# Sheet1.net
KiCad netlist of a schematic drawn in Altium Designer
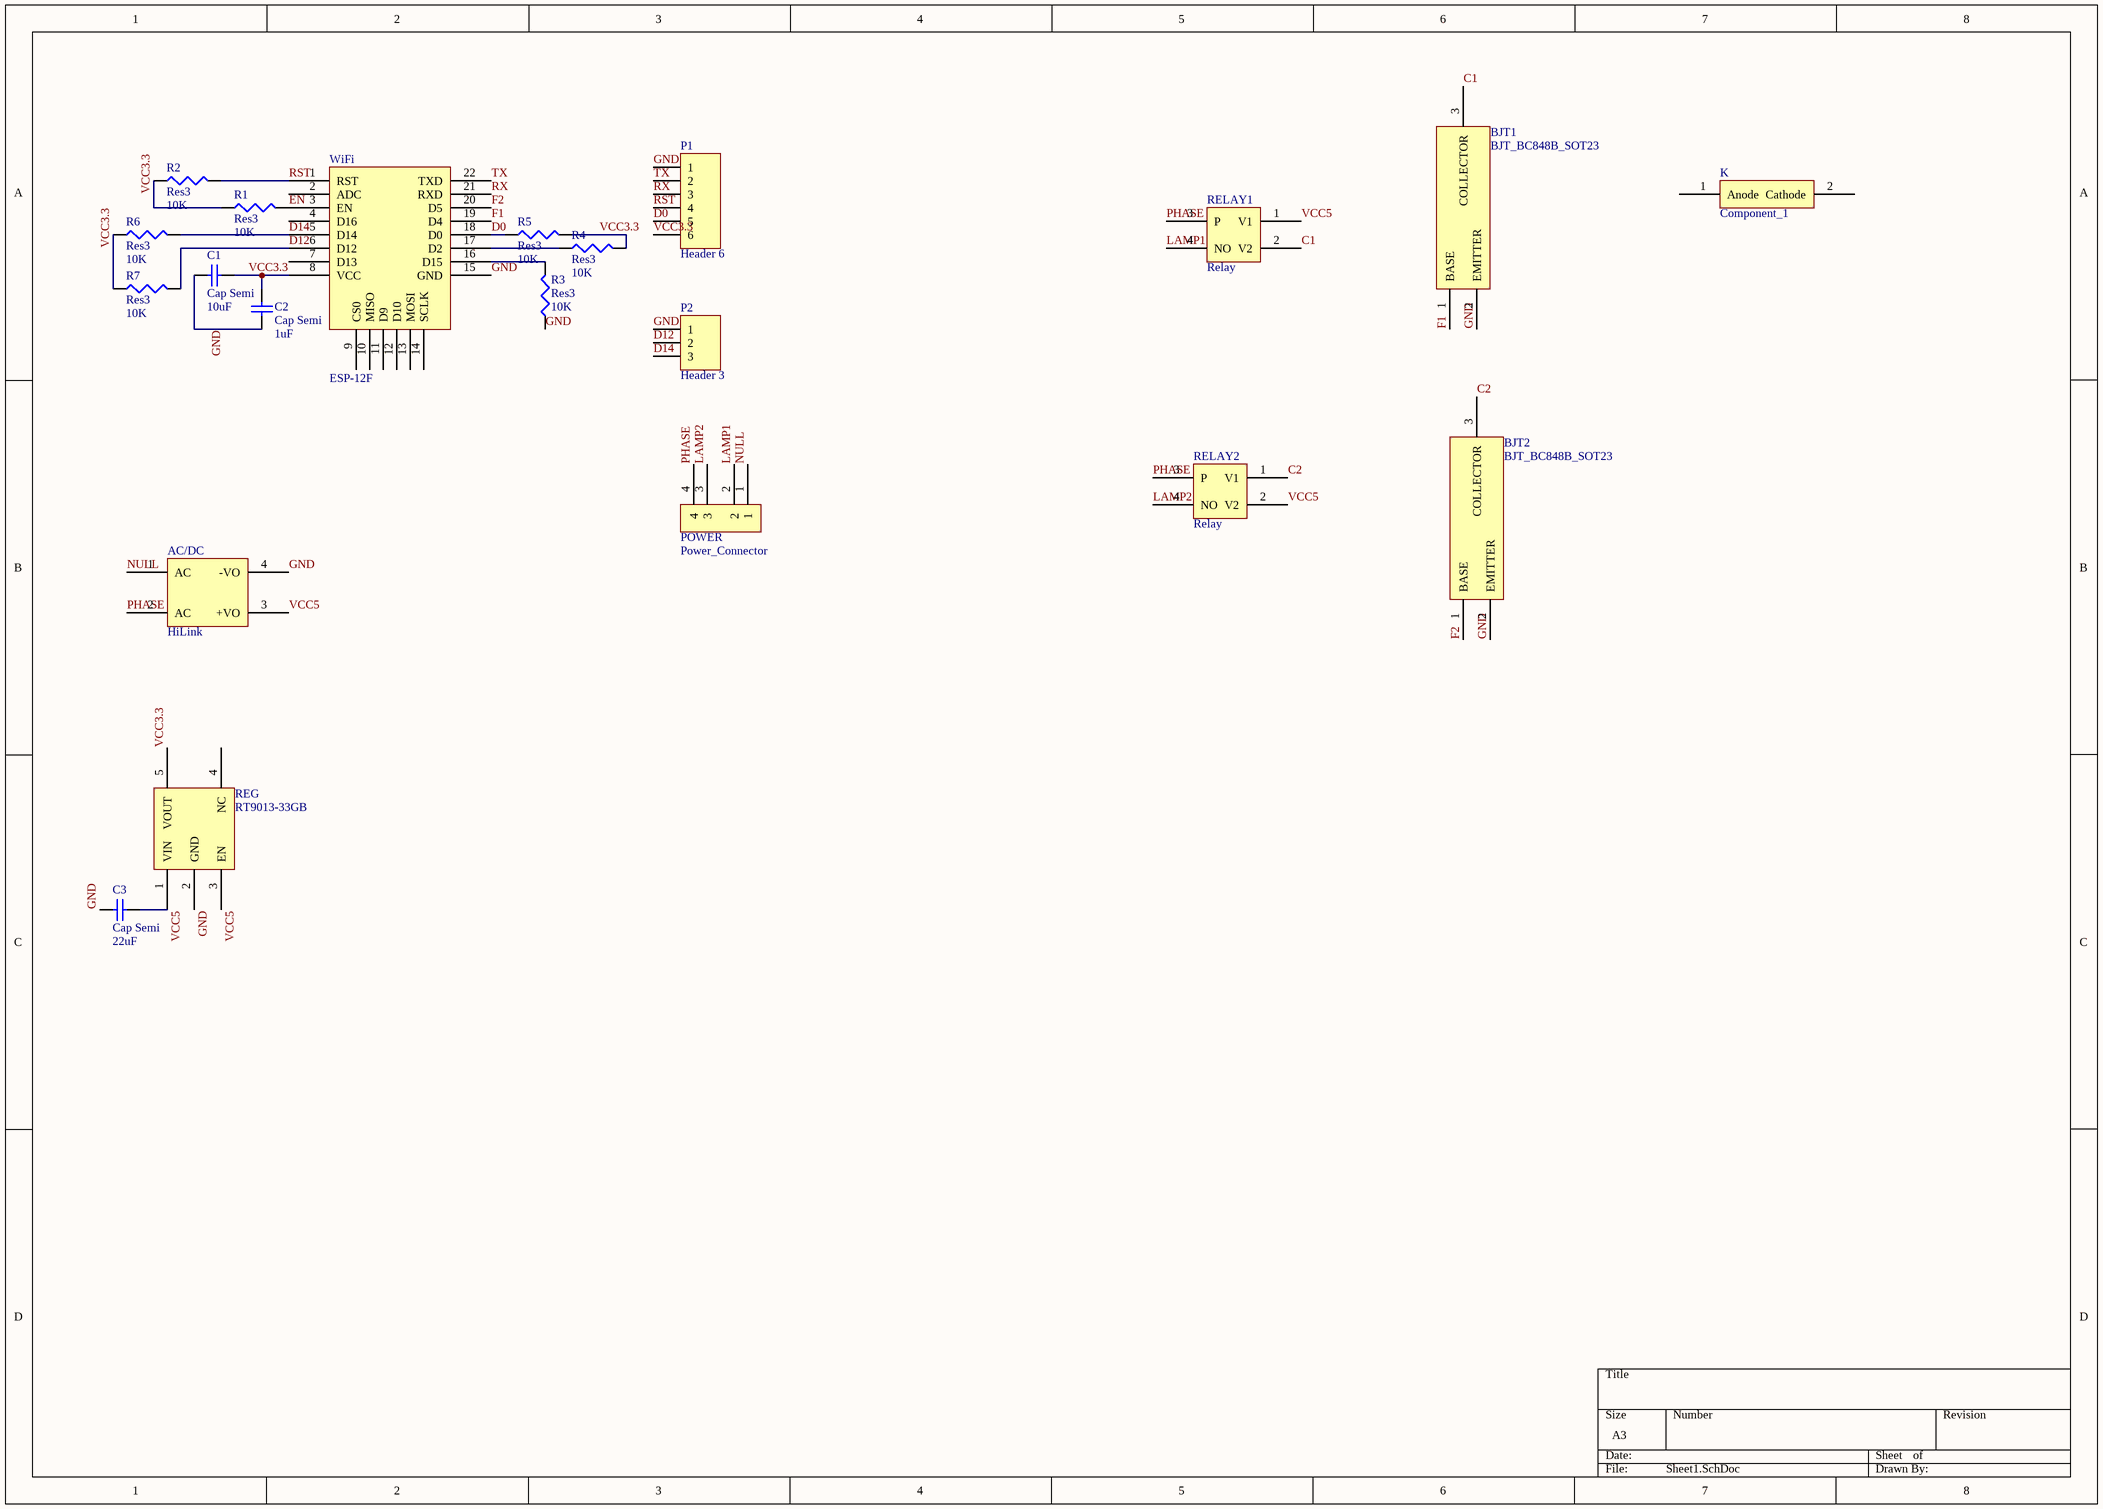
[diagram p0: Sheet1.SchDoc]

(export (version "E")
  (design (tool "Eeschema 10.0.6"))
  (components
    (comp (ref "AC/DC")
      (value "HiLink")
      (footprint "HiLink")
      (libsource (lib "Smart Switch") (part "HiLink"))
    )
    (comp (ref "BJT1")
      (value "BJT_BC848B_SOT23")
      (footprint "BJT_BC848B_SOT23")
      (libsource (lib "Smart Switch") (part "BJT_BC848B_SOT23"))
    )
    (comp (ref "BJT2")
      (value "BJT_BC848B_SOT23")
      (footprint "BJT_BC848B_SOT23")
      (libsource (lib "Smart Switch") (part "BJT_BC848B_SOT23"))
    )
    (comp (ref "C1")
      (value "Cap Semi")
      (footprint "C1206")
      (description "Capacitor (Semiconductor SIM Model)")
      (fields (field (name "ALTIUM_VALUE") "10uF") (field (name "PUBLISHER") "Altium Limited"))
      (libsource (lib "Miscellaneous Devices") (part "Cap Semi"))
    )
    (comp (ref "C2")
      (value "Cap Semi")
      (footprint "C1206")
      (description "Capacitor (Semiconductor SIM Model)")
      (fields (field (name "ALTIUM_VALUE") "1uF") (field (name "PUBLISHER") "Altium Limited"))
      (libsource (lib "Miscellaneous Devices") (part "Cap Semi"))
    )
    (comp (ref "C3")
      (value "Cap Semi")
      (footprint "C1206")
      (description "Capacitor (Semiconductor SIM Model)")
      (fields (field (name "ALTIUM_VALUE") "22uF") (field (name "PUBLISHER") "Altium Limited"))
      (libsource (lib "Miscellaneous Devices") (part "Cap Semi"))
    )
    (comp (ref "K")
      (value "Component_1")
      (footprint "PCBComponent_1")
      (libsource (lib "SS12-Diode") (part "Component_1"))
    )
    (comp (ref "P1")
      (value "Header 6")
      (footprint "HDR1X6")
      (description "Header, 6-Pin")
      (fields (field (name "PUBLISHER") "Altium Limited"))
      (libsource (lib "Miscellaneous Connectors") (part "Header 6"))
    )
    (comp (ref "P2")
      (value "Header 3")
      (footprint "HDR1X3")
      (description "Header, 3-Pin")
      (fields (field (name "PUBLISHER") "Altium Limited"))
      (libsource (lib "Miscellaneous Connectors") (part "Header 3"))
    )
    (comp (ref "POWER")
      (value "Power_Connector")
      (footprint "Power_Connector")
      (libsource (lib "SmartLIB2") (part "Power_Connector"))
    )
    (comp (ref "R1")
      (value "Res3")
      (footprint "J1-0603")
      (description "Resistor")
      (fields (field (name "ALTIUM_VALUE") "10K") (field (name "PUBLISHER") "Altium Limited"))
      (libsource (lib "Miscellaneous Devices") (part "Res3"))
    )
    (comp (ref "R2")
      (value "Res3")
      (footprint "J1-0603")
      (description "Resistor")
      (fields (field (name "ALTIUM_VALUE") "10K") (field (name "PUBLISHER") "Altium Limited"))
      (libsource (lib "Miscellaneous Devices") (part "Res3"))
    )
    (comp (ref "R3")
      (value "Res3")
      (footprint "J1-0603")
      (description "Resistor")
      (fields (field (name "ALTIUM_VALUE") "10K") (field (name "PUBLISHER") "Altium Limited"))
      (libsource (lib "Miscellaneous Devices") (part "Res3"))
    )
    (comp (ref "R4")
      (value "Res3")
      (footprint "J1-0603")
      (description "Resistor")
      (fields (field (name "ALTIUM_VALUE") "10K") (field (name "PUBLISHER") "Altium Limited"))
      (libsource (lib "Miscellaneous Devices") (part "Res3"))
    )
    (comp (ref "R5")
      (value "Res3")
      (footprint "J1-0603")
      (description "Resistor")
      (fields (field (name "ALTIUM_VALUE") "10K") (field (name "PUBLISHER") "Altium Limited"))
      (libsource (lib "Miscellaneous Devices") (part "Res3"))
    )
    (comp (ref "R6")
      (value "Res3")
      (footprint "J1-0603")
      (description "Resistor")
      (fields (field (name "ALTIUM_VALUE") "10K") (field (name "PUBLISHER") "Altium Limited"))
      (libsource (lib "Miscellaneous Devices") (part "Res3"))
    )
    (comp (ref "R7")
      (value "Res3")
      (footprint "J1-0603")
      (description "Resistor")
      (fields (field (name "ALTIUM_VALUE") "10K") (field (name "PUBLISHER") "Altium Limited"))
      (libsource (lib "Miscellaneous Devices") (part "Res3"))
    )
    (comp (ref "REG")
      (value "RT9013-33GB")
      (footprint "RT9013-33GB")
      (libsource (lib "SmartLIB2") (part "RT9013-33GB"))
    )
    (comp (ref "RELAY1") (value "Relay") (footprint "Relay") (libsource (lib "SmartLIB2") (part "Relay")))
    (comp (ref "RELAY2") (value "Relay") (footprint "Relay") (libsource (lib "SmartLIB2") (part "Relay")))
    (comp (ref "WiFi") (value "ESP-12F") (footprint "ESP-12F") (libsource (lib "SmartLIB2") (part "ESP-12F")))
  )
  (nets
    (net (code "1") (name "/C1") (class "Default")
      (node (ref "BJT1") (pin "3") (pinfunction "COLLECTOR_3") (pintype "passive"))
      (node (ref "RELAY1") (pin "2") (pinfunction "V2_2") (pintype "passive"))
    )
    (net (code "2") (name "/C2") (class "Default")
      (node (ref "BJT2") (pin "3") (pinfunction "COLLECTOR_3") (pintype "passive"))
      (node (ref "RELAY2") (pin "1") (pinfunction "V1_1") (pintype "passive"))
    )
    (net (code "3") (name "/D0") (class "Default")
      (node (ref "P1") (pin "5") (pinfunction "5_5") (pintype "passive"))
      (node (ref "R5") (pin "1") (pinfunction "1_1") (pintype "passive"))
      (node (ref "WiFi") (pin "18") (pinfunction "D0_18") (pintype "passive"))
    )
    (net (code "4") (name "/D12") (class "Default")
      (node (ref "P2") (pin "2") (pinfunction "2_2") (pintype "passive"))
      (node (ref "R7") (pin "2") (pinfunction "2_2") (pintype "passive"))
      (node (ref "WiFi") (pin "6") (pinfunction "D12_6") (pintype "passive"))
    )
    (net (code "5") (name "/D14") (class "Default")
      (node (ref "P2") (pin "3") (pinfunction "3_3") (pintype "passive"))
      (node (ref "R6") (pin "2") (pinfunction "2_2") (pintype "passive"))
      (node (ref "WiFi") (pin "5") (pinfunction "D14_5") (pintype "passive"))
    )
    (net (code "6") (name "/EN") (class "Default")
      (node (ref "R1") (pin "2") (pinfunction "2_2") (pintype "passive"))
      (node (ref "WiFi") (pin "3") (pinfunction "EN_3") (pintype "passive"))
    )
    (net (code "7") (name "/F1") (class "Default")
      (node (ref "BJT1") (pin "1") (pinfunction "BASE_1") (pintype "passive"))
      (node (ref "WiFi") (pin "19") (pinfunction "D4_19") (pintype "passive"))
    )
    (net (code "8") (name "/F2") (class "Default")
      (node (ref "BJT2") (pin "1") (pinfunction "BASE_1") (pintype "passive"))
      (node (ref "WiFi") (pin "20") (pinfunction "D5_20") (pintype "passive"))
    )
    (net (code "9") (name "/GND") (class "Default")
      (node (ref "AC/DC") (pin "4") (pinfunction "-VO_4") (pintype "passive"))
      (node (ref "BJT1") (pin "2") (pinfunction "EMITTER_2") (pintype "passive"))
      (node (ref "BJT2") (pin "2") (pinfunction "EMITTER_2") (pintype "passive"))
      (node (ref "C1") (pin "1") (pinfunction "1_1") (pintype "passive"))
      (node (ref "C2") (pin "1") (pinfunction "1_1") (pintype "passive"))
      (node (ref "C3") (pin "2") (pinfunction "2_2") (pintype "passive"))
      (node (ref "P1") (pin "1") (pinfunction "1_1") (pintype "passive"))
      (node (ref "P2") (pin "1") (pinfunction "1_1") (pintype "passive"))
      (node (ref "R3") (pin "1") (pinfunction "1_1") (pintype "passive"))
      (node (ref "REG") (pin "2") (pinfunction "GND_2") (pintype "passive"))
      (node (ref "WiFi") (pin "15") (pinfunction "GND_15") (pintype "passive"))
    )
    (net (code "10") (name "/LAMP1") (class "Default")
      (node (ref "POWER") (pin "2") (pinfunction "2_2") (pintype "passive"))
      (node (ref "RELAY1") (pin "4") (pinfunction "NO_4") (pintype "passive"))
    )
    (net (code "11") (name "/LAMP2") (class "Default")
      (node (ref "POWER") (pin "3") (pinfunction "3_3") (pintype "passive"))
      (node (ref "RELAY2") (pin "4") (pinfunction "NO_4") (pintype "passive"))
    )
    (net (code "12") (name "/NULL") (class "Default")
      (node (ref "AC/DC") (pin "1") (pinfunction "AC_1") (pintype "passive"))
      (node (ref "POWER") (pin "1") (pinfunction "1_1") (pintype "passive"))
    )
    (net (code "13") (name "/PHASE") (class "Default")
      (node (ref "AC/DC") (pin "2") (pinfunction "AC_2") (pintype "passive"))
      (node (ref "POWER") (pin "4") (pinfunction "4_4") (pintype "passive"))
      (node (ref "RELAY1") (pin "3") (pinfunction "P_3") (pintype "passive"))
      (node (ref "RELAY2") (pin "3") (pinfunction "P_3") (pintype "passive"))
    )
    (net (code "14") (name "/RST") (class "Default")
      (node (ref "P1") (pin "4") (pinfunction "4_4") (pintype "passive"))
      (node (ref "R2") (pin "2") (pinfunction "2_2") (pintype "passive"))
      (node (ref "WiFi") (pin "1") (pinfunction "RST_1") (pintype "passive"))
    )
    (net (code "15") (name "/RX") (class "Default")
      (node (ref "P1") (pin "3") (pinfunction "3_3") (pintype "passive"))
      (node (ref "WiFi") (pin "21") (pinfunction "RXD_21") (pintype "passive"))
    )
    (net (code "16") (name "/TX") (class "Default")
      (node (ref "P1") (pin "2") (pinfunction "2_2") (pintype "passive"))
      (node (ref "WiFi") (pin "22") (pinfunction "TXD_22") (pintype "passive"))
    )
    (net (code "17") (name "/VCC3.3") (class "Default")
      (node (ref "C1") (pin "2") (pinfunction "2_2") (pintype "passive"))
      (node (ref "C2") (pin "2") (pinfunction "2_2") (pintype "passive"))
      (node (ref "P1") (pin "6") (pinfunction "6_6") (pintype "passive"))
      (node (ref "R1") (pin "1") (pinfunction "1_1") (pintype "passive"))
      (node (ref "R2") (pin "1") (pinfunction "1_1") (pintype "passive"))
      (node (ref "R4") (pin "2") (pinfunction "2_2") (pintype "passive"))
      (node (ref "R5") (pin "2") (pinfunction "2_2") (pintype "passive"))
      (node (ref "R6") (pin "1") (pinfunction "1_1") (pintype "passive"))
      (node (ref "R7") (pin "1") (pinfunction "1_1") (pintype "passive"))
      (node (ref "REG") (pin "5") (pinfunction "VOUT_5") (pintype "passive"))
      (node (ref "WiFi") (pin "8") (pinfunction "VCC_8") (pintype "passive"))
    )
    (net (code "18") (name "/VCC5") (class "Default")
      (node (ref "AC/DC") (pin "3") (pinfunction "+VO_3") (pintype "passive"))
      (node (ref "C3") (pin "1") (pinfunction "1_1") (pintype "passive"))
      (node (ref "REG") (pin "1") (pinfunction "VIN_1") (pintype "passive"))
      (node (ref "REG") (pin "3") (pinfunction "EN_3") (pintype "passive"))
      (node (ref "RELAY1") (pin "1") (pinfunction "V1_1") (pintype "passive"))
      (node (ref "RELAY2") (pin "2") (pinfunction "V2_2") (pintype "passive"))
    )
    (net (code "19") (name "Net-(WiFi-D2)") (class "Default")
      (node (ref "R4") (pin "1") (pinfunction "1_1") (pintype "passive"))
      (node (ref "WiFi") (pin "17") (pinfunction "D2_17") (pintype "passive"))
    )
    (net (code "20") (name "Net-(WiFi-D15)") (class "Default")
      (node (ref "R3") (pin "2") (pinfunction "2_2") (pintype "passive"))
      (node (ref "WiFi") (pin "16") (pinfunction "D15_16") (pintype "passive"))
    )
    (net (code "21") (name "unconnected-(K-Anode-Pad1)") (class "Default")
      (node (ref "K") (pin "1") (pinfunction "Anode_1") (pintype "passive"))
    )
    (net (code "22") (name "unconnected-(K-Cathode-Pad2)") (class "Default")
      (node (ref "K") (pin "2") (pinfunction "Cathode_2") (pintype "passive"))
    )
    (net (code "23") (name "unconnected-(REG-NC-Pad4)") (class "Default")
      (node (ref "REG") (pin "4") (pinfunction "NC_4") (pintype "passive"))
    )
    (net (code "24") (name "unconnected-(WiFi-ADC-Pad2)") (class "Default")
      (node (ref "WiFi") (pin "2") (pinfunction "ADC_2") (pintype "passive"))
    )
    (net (code "25") (name "unconnected-(WiFi-CS0-Pad9)") (class "Default")
      (node (ref "WiFi") (pin "9") (pinfunction "CS0_9") (pintype "passive"))
    )
    (net (code "26") (name "unconnected-(WiFi-D9-Pad11)") (class "Default")
      (node (ref "WiFi") (pin "11") (pinfunction "D9_11") (pintype "passive"))
    )
    (net (code "27") (name "unconnected-(WiFi-D10-Pad12)") (class "Default")
      (node (ref "WiFi") (pin "12") (pinfunction "D10_12") (pintype "passive"))
    )
    (net (code "28") (name "unconnected-(WiFi-D13-Pad7)") (class "Default")
      (node (ref "WiFi") (pin "7") (pinfunction "D13_7") (pintype "passive"))
    )
    (net (code "29") (name "unconnected-(WiFi-D16-Pad4)") (class "Default")
      (node (ref "WiFi") (pin "4") (pinfunction "D16_4") (pintype "passive"))
    )
    (net (code "30") (name "unconnected-(WiFi-MISO-Pad10)") (class "Default")
      (node (ref "WiFi") (pin "10") (pinfunction "MISO_10") (pintype "passive"))
    )
    (net (code "31") (name "unconnected-(WiFi-MOSI-Pad13)") (class "Default")
      (node (ref "WiFi") (pin "13") (pinfunction "MOSI_13") (pintype "passive"))
    )
    (net (code "32") (name "unconnected-(WiFi-SCLK-Pad14)") (class "Default")
      (node (ref "WiFi") (pin "14") (pinfunction "SCLK_14") (pintype "passive"))
    )
  )
)
